# video_in_gps_mems.net
KiCad netlist of a schematic drawn in Altium Designer
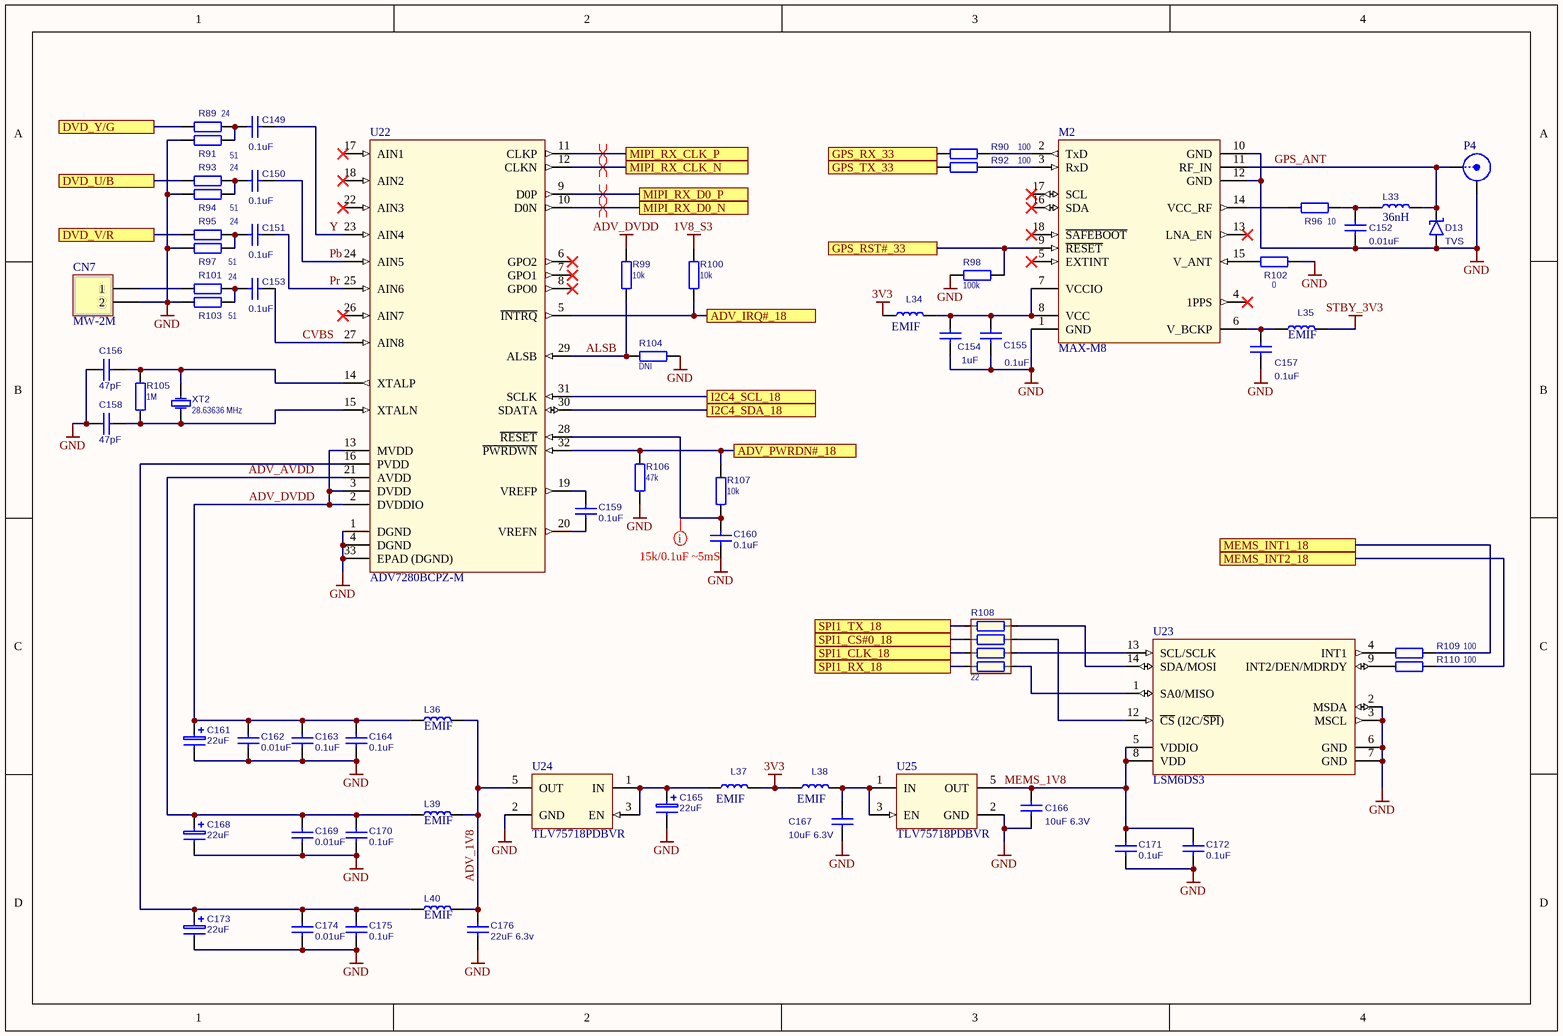
[diagram p0: video_in_gps_mems.SchDoc]

(export (version "E")
  (design (tool "Eeschema 10.0.6"))
  (components
    (comp (ref "C149")
      (value "0.1uF")
      (footprint "Capacitors:C0603")
      (description "CAP_NPOL")
      (fields (field (name "Comment") "C1608X7R1H104K080AA"))
      (libsource (lib "capacitors") (part "CAP_NPOL"))
    )
    (comp (ref "C150")
      (value "0.1uF")
      (footprint "Capacitors:C0603")
      (description "CAP_NPOL")
      (fields (field (name "Comment") "C1608X7R1H104K080AA"))
      (libsource (lib "capacitors") (part "CAP_NPOL"))
    )
    (comp (ref "C151")
      (value "0.1uF")
      (footprint "Capacitors:C0603")
      (description "CAP_NPOL")
      (fields (field (name "Comment") "C1608X7R1H104K080AA"))
      (libsource (lib "capacitors") (part "CAP_NPOL"))
    )
    (comp (ref "C152")
      (value "0.01uF")
      (footprint "Capacitors:C0603")
      (description "CAP_NPOL")
      (fields (field (name "Comment") "CL10B103KB8NNNC"))
      (libsource (lib "capacitors") (part "CAP_NPOL"))
    )
    (comp (ref "C153")
      (value "0.1uF")
      (footprint "Capacitors:C0603")
      (description "CAP_NPOL")
      (fields (field (name "Comment") "C1608X7R1H104K080AA"))
      (libsource (lib "capacitors") (part "CAP_NPOL"))
    )
    (comp (ref "C154")
      (value "1uF")
      (footprint "Capacitors:C0603")
      (description "CAP_NPOL")
      (fields (field (name "Comment") "CC0603KRX7R9BB105"))
      (libsource (lib "capacitors") (part "CAP_NPOL"))
    )
    (comp (ref "C155")
      (value "0.1uF")
      (footprint "Capacitors:C0603")
      (description "CAP_NPOL")
      (fields (field (name "Comment") "C1608X7R1H104K080AA"))
      (libsource (lib "capacitors") (part "CAP_NPOL"))
    )
    (comp (ref "C156")
      (value "47pF")
      (footprint "Capacitors:C0603")
      (description "CAP_NPOL")
      (fields (field (name "Comment") "CC0603JRNPO9BN470"))
      (libsource (lib "capacitors") (part "CAP_NPOL"))
    )
    (comp (ref "C157")
      (value "0.1uF")
      (footprint "Capacitors:C0603")
      (description "CAP_NPOL")
      (fields (field (name "Comment") "C1608X7R1H104K080AA"))
      (libsource (lib "capacitors") (part "CAP_NPOL"))
    )
    (comp (ref "C158")
      (value "47pF")
      (footprint "Capacitors:C0603")
      (description "CAP_NPOL")
      (fields (field (name "Comment") "CC0603JRNPO9BN470"))
      (libsource (lib "capacitors") (part "CAP_NPOL"))
    )
    (comp (ref "C159")
      (value "0.1uF")
      (footprint "Capacitors:C0603")
      (description "CAP_NPOL")
      (fields (field (name "Comment") "C1608X7R1H104K080AA"))
      (libsource (lib "capacitors") (part "CAP_NPOL"))
    )
    (comp (ref "C160")
      (value "0.1uF")
      (footprint "Capacitors:C0603")
      (description "CAP_NPOL")
      (fields (field (name "Comment") "C1608X7R1H104K080AA"))
      (libsource (lib "capacitors") (part "CAP_NPOL"))
    )
    (comp (ref "C161")
      (value "22uF")
      (footprint "Capacitors:TANTAL-A-1206")
      (description "CAP_POL")
      (fields (field (name "Comment") "293D226X9010A2TE3"))
      (libsource (lib "capacitors") (part "CAP_POL"))
    )
    (comp (ref "C162")
      (value "0.01uF")
      (footprint "Capacitors:C0603")
      (description "CAP_NPOL")
      (fields (field (name "Comment") "CL10B103KB8NNNC"))
      (libsource (lib "capacitors") (part "CAP_NPOL"))
    )
    (comp (ref "C163")
      (value "0.1uF")
      (footprint "Capacitors:C0603")
      (description "CAP_NPOL")
      (fields (field (name "Comment") "C1608X7R1H104K080AA"))
      (libsource (lib "capacitors") (part "CAP_NPOL"))
    )
    (comp (ref "C164")
      (value "0.1uF")
      (footprint "Capacitors:C0603")
      (description "CAP_NPOL")
      (fields (field (name "Comment") "C1608X7R1H104K080AA"))
      (libsource (lib "capacitors") (part "CAP_NPOL"))
    )
    (comp (ref "C165")
      (value "22uF")
      (footprint "Capacitors:TANTAL-A-1206")
      (description "CAP_POL")
      (fields (field (name "Comment") "293D226X9010A2TE3"))
      (libsource (lib "capacitors") (part "CAP_POL"))
    )
    (comp (ref "C166")
      (value "10uF 6.3V")
      (footprint "Capacitors:C0603")
      (description "CAP_NPOL")
      (fields (field (name "Comment") "CC0603MRX5R5BB106"))
      (libsource (lib "capacitors") (part "CAP_NPOL"))
    )
    (comp (ref "C167")
      (value "10uF 6.3V")
      (footprint "Capacitors:C0603")
      (description "CAP_NPOL")
      (fields (field (name "Comment") "CC0603MRX5R5BB106"))
      (libsource (lib "capacitors") (part "CAP_NPOL"))
    )
    (comp (ref "C168")
      (value "22uF")
      (footprint "Capacitors:TANTAL-A-1206")
      (description "CAP_POL")
      (fields (field (name "Comment") "293D226X9010A2TE3"))
      (libsource (lib "capacitors") (part "CAP_POL"))
    )
    (comp (ref "C169")
      (value "0.01uF")
      (footprint "Capacitors:C0603")
      (description "CAP_NPOL")
      (fields (field (name "Comment") "CL10B103KB8NNNC"))
      (libsource (lib "capacitors") (part "CAP_NPOL"))
    )
    (comp (ref "C170")
      (value "0.1uF")
      (footprint "Capacitors:C0603")
      (description "CAP_NPOL")
      (fields (field (name "Comment") "C1608X7R1H104K080AA"))
      (libsource (lib "capacitors") (part "CAP_NPOL"))
    )
    (comp (ref "C171")
      (value "0.1uF")
      (footprint "Capacitors:C0603")
      (description "CAP_NPOL")
      (fields (field (name "Comment") "C1608X7R1H104K080AA"))
      (libsource (lib "capacitors") (part "CAP_NPOL"))
    )
    (comp (ref "C172")
      (value "0.1uF")
      (footprint "Capacitors:C0603")
      (description "CAP_NPOL")
      (fields (field (name "Comment") "C1608X7R1H104K080AA"))
      (libsource (lib "capacitors") (part "CAP_NPOL"))
    )
    (comp (ref "C173")
      (value "22uF")
      (footprint "Capacitors:TANTAL-A-1206")
      (description "CAP_POL")
      (fields (field (name "Comment") "293D226X9010A2TE3"))
      (libsource (lib "capacitors") (part "CAP_POL"))
    )
    (comp (ref "C174")
      (value "0.01uF")
      (footprint "Capacitors:C0603")
      (description "CAP_NPOL")
      (fields (field (name "Comment") "CL10B103KB8NNNC"))
      (libsource (lib "capacitors") (part "CAP_NPOL"))
    )
    (comp (ref "C175")
      (value "0.1uF")
      (footprint "Capacitors:C0603")
      (description "CAP_NPOL")
      (fields (field (name "Comment") "C1608X7R1H104K080AA"))
      (libsource (lib "capacitors") (part "CAP_NPOL"))
    )
    (comp (ref "C176")
      (value "22uF 6.3v")
      (footprint "Capacitors:C0805")
      (description "CAP_NPOL")
      (fields (field (name "Comment") "CL21A226MQQNNNE"))
      (libsource (lib "capacitors") (part "CAP_NPOL"))
    )
    (comp (ref "CN7")
      (value "MW-2M")
      (footprint "MW-2M")
      (description "Header, 2-Pin")
      (fields (field (name "PUBLISHER") "Altium Limited"))
      (libsource (lib "HDR") (part "HDR 2"))
    )
    (comp (ref "D13")
      (value "TVS")
      (footprint "SOD-323")
      (description "CDSOD323-T05LC")
      (libsource (lib "diodes") (part "SHOTTKY"))
    )
    (comp (ref "L33")
      (value "36nH")
      (footprint "IND0603")
      (description "IND_WO_IRON")
      (fields (field (name "Comment") "LQW18AN36NG00D"))
      (libsource (lib "inductors") (part "IND_WO_IRON"))
    )
    (comp (ref "L34")
      (value "EMIF")
      (footprint "IND0603")
      (description "IND_WO_IRON")
      (fields (field (name "Comment") "BLM18AG102SN1D"))
      (libsource (lib "inductors") (part "IND_WO_IRON"))
    )
    (comp (ref "L35")
      (value "EMIF")
      (footprint "IND0603")
      (description "IND_WO_IRON")
      (fields (field (name "Comment") "BLM18AG102SN1D"))
      (libsource (lib "inductors") (part "IND_WO_IRON"))
    )
    (comp (ref "L36")
      (value "EMIF")
      (footprint "IND0603")
      (description "IND_WO_IRON")
      (fields (field (name "Comment") "BLM18AG102SN1D"))
      (libsource (lib "inductors") (part "IND_WO_IRON"))
    )
    (comp (ref "L37")
      (value "EMIF")
      (footprint "IND0603")
      (description "IND_WO_IRON")
      (fields (field (name "Comment") "BLM18AG102SN1D"))
      (libsource (lib "inductors") (part "IND_WO_IRON"))
    )
    (comp (ref "L38")
      (value "EMIF")
      (footprint "IND0603")
      (description "IND_WO_IRON")
      (fields (field (name "Comment") "BLM18AG102SN1D"))
      (libsource (lib "inductors") (part "IND_WO_IRON"))
    )
    (comp (ref "L39")
      (value "EMIF")
      (footprint "IND0603")
      (description "IND_WO_IRON")
      (fields (field (name "Comment") "BLM18AG102SN1D"))
      (libsource (lib "inductors") (part "IND_WO_IRON"))
    )
    (comp (ref "L40")
      (value "EMIF")
      (footprint "IND0603")
      (description "IND_WO_IRON")
      (fields (field (name "Comment") "BLM18AG102SN1D"))
      (libsource (lib "inductors") (part "IND_WO_IRON"))
    )
    (comp (ref "M2")
      (value "MAX-M8")
      (footprint "GNSS:MAX-M8")
      (description "MAX-M8 concurrent GNSS modules")
      (libsource (lib "GNSS") (part "MAX-M8"))
    )
    (comp (ref "P4")
      (value "I-PEX")
      (footprint "RF:I-PEX")
      (fields (field (name "PUBLISHER") "Altium Limited"))
      (libsource (lib "Miscellaneous Connectors") (part "BNC"))
    )
    (comp (ref "R89")
      (value "24")
      (footprint "R0603")
      (description "RES")
      (libsource (lib "resistors") (part "RESISTOR"))
    )
    (comp (ref "R90")
      (value "100")
      (footprint "R0603")
      (description "RES")
      (libsource (lib "resistors") (part "RESISTOR"))
    )
    (comp (ref "R91")
      (value "51")
      (footprint "R0603")
      (description "RES")
      (libsource (lib "resistors") (part "RESISTOR"))
    )
    (comp (ref "R92")
      (value "100")
      (footprint "R0603")
      (description "RES")
      (libsource (lib "resistors") (part "RESISTOR"))
    )
    (comp (ref "R93")
      (value "24")
      (footprint "R0603")
      (description "RES")
      (libsource (lib "resistors") (part "RESISTOR"))
    )
    (comp (ref "R94")
      (value "51")
      (footprint "R0603")
      (description "RES")
      (libsource (lib "resistors") (part "RESISTOR"))
    )
    (comp (ref "R95")
      (value "24")
      (footprint "R0603")
      (description "RES")
      (libsource (lib "resistors") (part "RESISTOR"))
    )
    (comp (ref "R96")
      (value "10")
      (footprint "R0603")
      (description "RES")
      (libsource (lib "resistors") (part "RESISTOR"))
    )
    (comp (ref "R97")
      (value "51")
      (footprint "R0603")
      (description "RES")
      (libsource (lib "resistors") (part "RESISTOR"))
    )
    (comp (ref "R98")
      (value "100k")
      (footprint "R0603")
      (description "RES")
      (libsource (lib "resistors") (part "RESISTOR"))
    )
    (comp (ref "R99")
      (value "10k")
      (footprint "R0603")
      (description "RES")
      (libsource (lib "resistors") (part "RESISTOR"))
    )
    (comp (ref "R100")
      (value "10k")
      (footprint "R0603")
      (description "RES")
      (libsource (lib "resistors") (part "RESISTOR"))
    )
    (comp (ref "R101")
      (value "24")
      (footprint "R0603")
      (description "RES")
      (libsource (lib "resistors") (part "RESISTOR"))
    )
    (comp (ref "R102")
      (value "0")
      (footprint "R0603")
      (description "RES")
      (libsource (lib "resistors") (part "RESISTOR"))
    )
    (comp (ref "R103")
      (value "51")
      (footprint "R0603")
      (description "RES")
      (libsource (lib "resistors") (part "RESISTOR"))
    )
    (comp (ref "R104")
      (value "DNI")
      (footprint "R0603")
      (description "RES")
      (libsource (lib "resistors") (part "RESISTOR"))
    )
    (comp (ref "R105")
      (value "1M")
      (footprint "R0603")
      (description "RES")
      (libsource (lib "resistors") (part "RESISTOR"))
    )
    (comp (ref "R106")
      (value "47k")
      (footprint "R0603")
      (description "RES")
      (libsource (lib "resistors") (part "RESISTOR"))
    )
    (comp (ref "R107")
      (value "10k")
      (footprint "R0603")
      (description "RES")
      (libsource (lib "resistors") (part "RESISTOR"))
    )
    (comp (ref "R108")
      (value "22")
      (footprint "Resistors:R0804X4")
      (description "ARRAY")
      (fields (field (name "Comment") "TC124-JR-0722RL"))
      (libsource (lib "resistors") (part "ARRAY"))
    )
    (comp (ref "R109")
      (value "100")
      (footprint "R0603")
      (description "RES")
      (libsource (lib "resistors") (part "RESISTOR"))
    )
    (comp (ref "R110")
      (value "100")
      (footprint "R0603")
      (description "RES")
      (libsource (lib "resistors") (part "RESISTOR"))
    )
    (comp (ref "U22")
      (value "ADV7280BCPZ-M")
      (footprint "CP-32-12")
      (description "10-Bit, 4xOversampling SDTV Video Decoder")
      (libsource (lib "ADV7280") (part "ADV7280BCPZ-M"))
    )
    (comp (ref "U23")
      (value "LSM6DS3")
      (footprint "LGA-14 (2.5x3.0x0.86)")
      (description "iNEMO inertial module:\r\n always-on 3D accelerometer and 3D gyroscope")
      (libsource (lib "LSM6DS3") (part "LSM6DS3"))
    )
    (comp (ref "U24")
      (value "TLV75718PDBVR")
      (footprint "SOT-23-5")
      (description "Capacitor-Free, 300-mA, Low-Dropout Regulator with Foldback Current Limit for Portable Devices")
      (libsource (lib "") (part "TLV733P_1"))
    )
    (comp (ref "U25")
      (value "TLV75718PDBVR")
      (footprint "SOT-23-5")
      (description "Capacitor-Free, 300-mA, Low-Dropout Regulator with Foldback Current Limit for Portable Devices")
      (libsource (lib "TLV733P") (part "TLV733P"))
    )
    (comp (ref "XT2")
      (value "28.63636 MHz")
      (footprint "HC-49/S-SMD")
      (description "Xtal")
      (libsource (lib "xtal") (part "XTAL"))
    )
  )
  (nets
    (net (code "1") (name "/ADV_1V8") (class "Default")
      (node (ref "C176") (pin "2") (pinfunction "2_2") (pintype "passive"))
      (node (ref "L36") (pin "2") (pintype "passive"))
      (node (ref "L39") (pin "2") (pintype "passive"))
      (node (ref "L40") (pin "2") (pintype "passive"))
      (node (ref "U24") (pin "5") (pinfunction "OUT_5") (pintype "power_in"))
    )
    (net (code "2") (name "/ADV_AVDD") (class "Default")
      (node (ref "C168") (pin "1") (pinfunction "+_1") (pintype "passive"))
      (node (ref "C169") (pin "1") (pinfunction "1_1") (pintype "passive"))
      (node (ref "C170") (pin "1") (pinfunction "1_1") (pintype "passive"))
      (node (ref "L39") (pin "1") (pintype "passive"))
      (node (ref "U22") (pin "21") (pinfunction "AVDD_21") (pintype "power_in"))
    )
    (net (code "3") (name "/ADV_IRQ#_18") (class "Default")
      (node (ref "R100") (pin "1") (pinfunction "1_1") (pintype "passive"))
      (node (ref "U22") (pin "5") (pinfunction "~{INTRQ}_5") (pintype "output"))
    )
    (net (code "4") (name "/ADV_PWRDN#_18") (class "Default")
      (node (ref "R106") (pin "2") (pinfunction "2_2") (pintype "passive"))
      (node (ref "R107") (pin "1") (pinfunction "1_1") (pintype "passive"))
      (node (ref "U22") (pin "32") (pinfunction "~{PWRDWN}_32") (pintype "input"))
    )
    (net (code "5") (name "/ALSB") (class "Default")
      (node (ref "R104") (pin "2") (pinfunction "2_2") (pintype "passive"))
      (node (ref "R99") (pin "1") (pinfunction "1_1") (pintype "passive"))
      (node (ref "U22") (pin "29") (pinfunction "ALSB_29") (pintype "input"))
    )
    (net (code "6") (name "/CVBS") (class "Default")
      (node (ref "C153") (pin "1") (pinfunction "1_1") (pintype "passive"))
      (node (ref "U22") (pin "27") (pinfunction "AIN8_27") (pintype "input"))
    )
    (net (code "7") (name "/DVD_U{slash}B") (class "Default")
      (node (ref "R93") (pin "2") (pinfunction "2_2") (pintype "passive"))
    )
    (net (code "8") (name "/DVD_V{slash}R") (class "Default")
      (node (ref "R95") (pin "2") (pinfunction "2_2") (pintype "passive"))
    )
    (net (code "9") (name "/DVD_Y{slash}G") (class "Default")
      (node (ref "R89") (pin "2") (pinfunction "2_2") (pintype "passive"))
    )
    (net (code "10") (name "/GPS_ANT") (class "Default")
      (node (ref "D13") (pin "2") (pinfunction "K_2") (pintype "passive"))
      (node (ref "L33") (pin "2") (pintype "passive"))
      (node (ref "M2") (pin "11") (pinfunction "RF_IN_11") (pintype "passive"))
      (node (ref "P4") (pin "1") (pinfunction "X_1") (pintype "passive"))
    )
    (net (code "11") (name "/GPS_RST#_33") (class "Default")
      (node (ref "M2") (pin "9") (pinfunction "~{RESET}_9") (pintype "input"))
      (node (ref "R98") (pin "2") (pinfunction "2_2") (pintype "passive"))
    )
    (net (code "12") (name "/GPS_RX_33") (class "Default")
      (node (ref "R90") (pin "2") (pinfunction "2_2") (pintype "passive"))
    )
    (net (code "13") (name "/GPS_TX_33") (class "Default")
      (node (ref "R92") (pin "2") (pinfunction "2_2") (pintype "passive"))
    )
    (net (code "14") (name "/I2C4_SCL_18") (class "Default")
      (node (ref "U22") (pin "31") (pinfunction "SCLK_31") (pintype "input"))
    )
    (net (code "15") (name "/I2C4_SDA_18") (class "Default")
      (node (ref "U22") (pin "30") (pinfunction "SDATA_30") (pintype "bidirectional"))
    )
    (net (code "16") (name "/MEMS_1V8") (class "Default")
      (node (ref "C166") (pin "1") (pinfunction "1_1") (pintype "passive"))
      (node (ref "C171") (pin "1") (pinfunction "1_1") (pintype "passive"))
      (node (ref "C172") (pin "1") (pinfunction "1_1") (pintype "passive"))
      (node (ref "U23") (pin "5") (pinfunction "VDDIO_5") (pintype "passive"))
      (node (ref "U23") (pin "8") (pinfunction "VDD_8") (pintype "power_in"))
      (node (ref "U25") (pin "5") (pinfunction "OUT_5") (pintype "power_in"))
    )
    (net (code "17") (name "/MEMS_INT1_18") (class "Default")
      (node (ref "R109") (pin "1") (pinfunction "1_1") (pintype "passive"))
    )
    (net (code "18") (name "/MEMS_INT2_18") (class "Default")
      (node (ref "R110") (pin "1") (pinfunction "1_1") (pintype "passive"))
    )
    (net (code "19") (name "/MIPI_RX_CLK_N") (class "Default")
      (node (ref "U22") (pin "12") (pinfunction "CLKN_12") (pintype "output"))
    )
    (net (code "20") (name "/MIPI_RX_CLK_P") (class "Default")
      (node (ref "U22") (pin "11") (pinfunction "CLKP_11") (pintype "output"))
    )
    (net (code "21") (name "/MIPI_RX_D0_N") (class "Default")
      (node (ref "U22") (pin "10") (pinfunction "D0N_10") (pintype "output"))
    )
    (net (code "22") (name "/MIPI_RX_D0_P") (class "Default")
      (node (ref "U22") (pin "9") (pinfunction "D0P_9") (pintype "output"))
    )
    (net (code "23") (name "/Pb") (class "Default")
      (node (ref "C150") (pin "1") (pinfunction "1_1") (pintype "passive"))
      (node (ref "U22") (pin "24") (pinfunction "AIN5_24") (pintype "input"))
    )
    (net (code "24") (name "/Pr") (class "Default")
      (node (ref "C151") (pin "1") (pinfunction "1_1") (pintype "passive"))
      (node (ref "U22") (pin "25") (pinfunction "AIN6_25") (pintype "input"))
    )
    (net (code "25") (name "/SPI1_CLK_18") (class "Default")
      (node (ref "R108") (pin "3") (pinfunction "3_3") (pintype "passive"))
    )
    (net (code "26") (name "/SPI1_CS#0_18") (class "Default")
      (node (ref "R108") (pin "5") (pinfunction "5_5") (pintype "passive"))
    )
    (net (code "27") (name "/SPI1_RX_18") (class "Default")
      (node (ref "R108") (pin "1") (pinfunction "1_1") (pintype "passive"))
    )
    (net (code "28") (name "/SPI1_TX_18") (class "Default")
      (node (ref "R108") (pin "7") (pinfunction "7_7") (pintype "passive"))
    )
    (net (code "29") (name "/Y") (class "Default")
      (node (ref "C149") (pin "1") (pinfunction "1_1") (pintype "passive"))
      (node (ref "U22") (pin "23") (pinfunction "AIN4_23") (pintype "input"))
    )
    (net (code "30") (name "1V8_S3") (class "Default")
      (node (ref "R100") (pin "2") (pinfunction "2_2") (pintype "passive"))
    )
    (net (code "31") (name "3V3") (class "Default")
      (node (ref "L34") (pin "1") (pintype "passive"))
      (node (ref "L37") (pin "2") (pintype "passive"))
      (node (ref "L38") (pin "1") (pintype "passive"))
    )
    (net (code "32") (name "ADV_DVDD") (class "Default")
      (node (ref "C161") (pin "1") (pinfunction "+_1") (pintype "passive"))
      (node (ref "C162") (pin "1") (pinfunction "1_1") (pintype "passive"))
      (node (ref "C163") (pin "1") (pinfunction "1_1") (pintype "passive"))
      (node (ref "C164") (pin "1") (pinfunction "1_1") (pintype "passive"))
      (node (ref "L36") (pin "1") (pintype "passive"))
      (node (ref "R99") (pin "2") (pinfunction "2_2") (pintype "passive"))
      (node (ref "U22") (pin "13") (pinfunction "MVDD_13") (pintype "power_in"))
      (node (ref "U22") (pin "2") (pinfunction "DVDDIO_2") (pintype "power_in"))
      (node (ref "U22") (pin "3") (pinfunction "DVDD_3") (pintype "power_in"))
    )
    (net (code "33") (name "GND") (class "Default")
      (node (ref "C152") (pin "2") (pinfunction "2_2") (pintype "passive"))
      (node (ref "C154") (pin "1") (pinfunction "1_1") (pintype "passive"))
      (node (ref "C155") (pin "2") (pinfunction "2_2") (pintype "passive"))
      (node (ref "C156") (pin "2") (pinfunction "2_2") (pintype "passive"))
      (node (ref "C157") (pin "2") (pinfunction "2_2") (pintype "passive"))
      (node (ref "C158") (pin "2") (pinfunction "2_2") (pintype "passive"))
      (node (ref "C160") (pin "2") (pinfunction "2_2") (pintype "passive"))
      (node (ref "C161") (pin "2") (pinfunction "-_2") (pintype "passive"))
      (node (ref "C162") (pin "2") (pinfunction "2_2") (pintype "passive"))
      (node (ref "C163") (pin "2") (pinfunction "2_2") (pintype "passive"))
      (node (ref "C164") (pin "2") (pinfunction "2_2") (pintype "passive"))
      (node (ref "C165") (pin "2") (pinfunction "-_2") (pintype "passive"))
      (node (ref "C166") (pin "2") (pinfunction "2_2") (pintype "passive"))
      (node (ref "C167") (pin "2") (pinfunction "2_2") (pintype "passive"))
      (node (ref "C168") (pin "2") (pinfunction "-_2") (pintype "passive"))
      (node (ref "C169") (pin "2") (pinfunction "2_2") (pintype "passive"))
      (node (ref "C170") (pin "2") (pinfunction "2_2") (pintype "passive"))
      (node (ref "C171") (pin "2") (pinfunction "2_2") (pintype "passive"))
      (node (ref "C172") (pin "2") (pinfunction "2_2") (pintype "passive"))
      (node (ref "C173") (pin "2") (pinfunction "-_2") (pintype "passive"))
      (node (ref "C174") (pin "2") (pinfunction "2_2") (pintype "passive"))
      (node (ref "C175") (pin "2") (pinfunction "2_2") (pintype "passive"))
      (node (ref "C176") (pin "1") (pinfunction "1_1") (pintype "passive"))
      (node (ref "CN7") (pin "2") (pinfunction "2_2") (pintype "passive"))
      (node (ref "D13") (pin "1") (pinfunction "A_1") (pintype "passive"))
      (node (ref "M2") (pin "1") (pinfunction "GND_1") (pintype "power_in"))
      (node (ref "M2") (pin "10") (pinfunction "GND_10") (pintype "power_in"))
      (node (ref "M2") (pin "12") (pinfunction "GND_12") (pintype "power_in"))
      (node (ref "P4") (pin "2") (pinfunction "Y_2") (pintype "passive"))
      (node (ref "R102") (pin "1") (pinfunction "1_1") (pintype "passive"))
      (node (ref "R103") (pin "1") (pinfunction "1_1") (pintype "passive"))
      (node (ref "R104") (pin "1") (pinfunction "1_1") (pintype "passive"))
      (node (ref "R106") (pin "1") (pinfunction "1_1") (pintype "passive"))
      (node (ref "R91") (pin "1") (pinfunction "1_1") (pintype "passive"))
      (node (ref "R94") (pin "1") (pinfunction "1_1") (pintype "passive"))
      (node (ref "R97") (pin "1") (pinfunction "1_1") (pintype "passive"))
      (node (ref "R98") (pin "1") (pinfunction "1_1") (pintype "passive"))
      (node (ref "U22") (pin "1") (pinfunction "DGND_1") (pintype "power_in"))
      (node (ref "U22") (pin "33") (pinfunction "EPAD_(DGND)_33") (pintype "power_in"))
      (node (ref "U22") (pin "4") (pinfunction "DGND_4") (pintype "power_in"))
      (node (ref "U23") (pin "2") (pinfunction "MSDA_2") (pintype "bidirectional"))
      (node (ref "U23") (pin "3") (pinfunction "MSCL_3") (pintype "output"))
      (node (ref "U23") (pin "6") (pinfunction "GND_6") (pintype "power_in"))
      (node (ref "U23") (pin "7") (pinfunction "GND_7") (pintype "power_in"))
      (node (ref "U24") (pin "2") (pinfunction "GND_2") (pintype "power_in"))
      (node (ref "U25") (pin "2") (pinfunction "GND_2") (pintype "power_in"))
    )
    (net (code "34") (name "Net-(C149-Pad2)") (class "Default")
      (node (ref "C149") (pin "2") (pinfunction "2_2") (pintype "passive"))
      (node (ref "R89") (pin "1") (pinfunction "1_1") (pintype "passive"))
      (node (ref "R91") (pin "2") (pinfunction "2_2") (pintype "passive"))
    )
    (net (code "35") (name "Net-(C150-Pad2)") (class "Default")
      (node (ref "C150") (pin "2") (pinfunction "2_2") (pintype "passive"))
      (node (ref "R93") (pin "1") (pinfunction "1_1") (pintype "passive"))
      (node (ref "R94") (pin "2") (pinfunction "2_2") (pintype "passive"))
    )
    (net (code "36") (name "Net-(C151-Pad2)") (class "Default")
      (node (ref "C151") (pin "2") (pinfunction "2_2") (pintype "passive"))
      (node (ref "R95") (pin "1") (pinfunction "1_1") (pintype "passive"))
      (node (ref "R97") (pin "2") (pinfunction "2_2") (pintype "passive"))
    )
    (net (code "37") (name "Net-(C152-Pad1)") (class "Default")
      (node (ref "C152") (pin "1") (pinfunction "1_1") (pintype "passive"))
      (node (ref "L33") (pin "1") (pintype "passive"))
      (node (ref "R96") (pin "1") (pinfunction "1_1") (pintype "passive"))
    )
    (net (code "38") (name "Net-(C153-Pad2)") (class "Default")
      (node (ref "C153") (pin "2") (pinfunction "2_2") (pintype "passive"))
      (node (ref "R101") (pin "1") (pinfunction "1_1") (pintype "passive"))
      (node (ref "R103") (pin "2") (pinfunction "2_2") (pintype "passive"))
    )
    (net (code "39") (name "Net-(C165-+)") (class "Default")
      (node (ref "C165") (pin "1") (pinfunction "+_1") (pintype "passive"))
      (node (ref "L37") (pin "1") (pintype "passive"))
      (node (ref "U24") (pin "1") (pinfunction "IN_1") (pintype "power_in"))
      (node (ref "U24") (pin "3") (pinfunction "EN_3") (pintype "input"))
    )
    (net (code "40") (name "Net-(C173-+)") (class "Default")
      (node (ref "C173") (pin "1") (pinfunction "+_1") (pintype "passive"))
      (node (ref "C174") (pin "1") (pinfunction "1_1") (pintype "passive"))
      (node (ref "C175") (pin "1") (pinfunction "1_1") (pintype "passive"))
      (node (ref "L40") (pin "1") (pintype "passive"))
      (node (ref "U22") (pin "16") (pinfunction "PVDD_16") (pintype "power_in"))
    )
    (net (code "41") (name "Net-(CN7-Pad1)") (class "Default")
      (node (ref "CN7") (pin "1") (pinfunction "1_1") (pintype "passive"))
      (node (ref "R101") (pin "2") (pinfunction "2_2") (pintype "passive"))
    )
    (net (code "42") (name "Net-(M2-RxD)") (class "Default")
      (node (ref "M2") (pin "3") (pinfunction "RxD_3") (pintype "input"))
      (node (ref "R92") (pin "1") (pinfunction "1_1") (pintype "passive"))
    )
    (net (code "43") (name "Net-(M2-TxD)") (class "Default")
      (node (ref "M2") (pin "2") (pinfunction "TxD_2") (pintype "output"))
      (node (ref "R90") (pin "1") (pinfunction "1_1") (pintype "passive"))
    )
    (net (code "44") (name "Net-(M2-VCC)") (class "Default")
      (node (ref "C154") (pin "2") (pinfunction "2_2") (pintype "passive"))
      (node (ref "C155") (pin "1") (pinfunction "1_1") (pintype "passive"))
      (node (ref "L34") (pin "2") (pintype "passive"))
      (node (ref "M2") (pin "7") (pinfunction "VCCIO_7") (pintype "power_in"))
      (node (ref "M2") (pin "8") (pinfunction "VCC_8") (pintype "power_in"))
    )
    (net (code "45") (name "Net-(M2-VCC_RF)") (class "Default")
      (node (ref "M2") (pin "14") (pinfunction "VCC_RF_14") (pintype "output"))
      (node (ref "R96") (pin "2") (pinfunction "2_2") (pintype "passive"))
    )
    (net (code "46") (name "Net-(M2-V_ANT)") (class "Default")
      (node (ref "M2") (pin "15") (pinfunction "V_ANT_15") (pintype "input"))
      (node (ref "R102") (pin "2") (pinfunction "2_2") (pintype "passive"))
    )
    (net (code "47") (name "Net-(M2-V_BCKP)") (class "Default")
      (node (ref "C157") (pin "1") (pinfunction "1_1") (pintype "passive"))
      (node (ref "L35") (pin "1") (pintype "passive"))
      (node (ref "M2") (pin "6") (pinfunction "V_BCKP_6") (pintype "power_in"))
    )
    (net (code "48") (name "Net-(U22-VREFN)") (class "Default")
      (node (ref "C159") (pin "2") (pinfunction "2_2") (pintype "passive"))
      (node (ref "U22") (pin "20") (pinfunction "VREFN_20") (pintype "output"))
    )
    (net (code "49") (name "Net-(U22-VREFP)") (class "Default")
      (node (ref "C159") (pin "1") (pinfunction "1_1") (pintype "passive"))
      (node (ref "U22") (pin "19") (pinfunction "VREFP_19") (pintype "output"))
    )
    (net (code "50") (name "Net-(U22-XTALN)") (class "Default")
      (node (ref "C158") (pin "1") (pinfunction "1_1") (pintype "passive"))
      (node (ref "R105") (pin "2") (pinfunction "2_2") (pintype "passive"))
      (node (ref "U22") (pin "15") (pinfunction "XTALN_15") (pintype "input"))
      (node (ref "XT2") (pin "2") (pintype "passive"))
    )
    (net (code "51") (name "Net-(U22-XTALP)") (class "Default")
      (node (ref "C156") (pin "1") (pinfunction "1_1") (pintype "passive"))
      (node (ref "R105") (pin "1") (pinfunction "1_1") (pintype "passive"))
      (node (ref "U22") (pin "14") (pinfunction "XTALP_14") (pintype "output"))
      (node (ref "XT2") (pin "1") (pintype "passive"))
    )
    (net (code "52") (name "Net-(U22-~{RESET})") (class "Default")
      (node (ref "C160") (pin "1") (pinfunction "1_1") (pintype "passive"))
      (node (ref "R107") (pin "2") (pinfunction "2_2") (pintype "passive"))
      (node (ref "U22") (pin "28") (pinfunction "~{RESET}_28") (pintype "input"))
    )
    (net (code "53") (name "Net-(U23-INT1)") (class "Default")
      (node (ref "R109") (pin "2") (pinfunction "2_2") (pintype "passive"))
      (node (ref "U23") (pin "4") (pinfunction "INT1_4") (pintype "output"))
    )
    (net (code "54") (name "Net-(U23-INT2{slash}DEN{slash}MDRDY)") (class "Default")
      (node (ref "R110") (pin "2") (pinfunction "2_2") (pintype "passive"))
      (node (ref "U23") (pin "9") (pinfunction "INT2/DEN/MDRDY_9") (pintype "bidirectional"))
    )
    (net (code "55") (name "Net-(U23-SA0{slash}MISO)") (class "Default")
      (node (ref "R108") (pin "2") (pinfunction "2_2") (pintype "passive"))
      (node (ref "U23") (pin "1") (pinfunction "SA0/MISO_1") (pintype "bidirectional"))
    )
    (net (code "56") (name "Net-(U23-SCL{slash}SCLK)") (class "Default")
      (node (ref "R108") (pin "4") (pinfunction "4_4") (pintype "passive"))
      (node (ref "U23") (pin "13") (pinfunction "SCL/SCLK_13") (pintype "input"))
    )
    (net (code "57") (name "Net-(U23-SDA{slash}MOSI)") (class "Default")
      (node (ref "R108") (pin "8") (pinfunction "8_8") (pintype "passive"))
      (node (ref "U23") (pin "14") (pinfunction "SDA/MOSI_14") (pintype "bidirectional"))
    )
    (net (code "58") (name "Net-(U23-~{CS}_(I2C{slash}~{SPI}))") (class "Default")
      (node (ref "R108") (pin "6") (pinfunction "6_6") (pintype "passive"))
      (node (ref "U23") (pin "12") (pinfunction "~{CS}_(I2C/~{SPI})_12") (pintype "input"))
    )
    (net (code "59") (name "Net-(U25-EN)") (class "Default")
      (node (ref "C167") (pin "1") (pinfunction "1_1") (pintype "passive"))
      (node (ref "L38") (pin "2") (pintype "passive"))
      (node (ref "U25") (pin "1") (pinfunction "IN_1") (pintype "power_in"))
      (node (ref "U25") (pin "3") (pinfunction "EN_3") (pintype "input"))
    )
    (net (code "60") (name "STBY_3V3") (class "Default") (node (ref "L35") (pin "2") (pintype "passive")))
    (net (code "61") (name "unconnected-(M2-1PPS-Pad4)") (class "Default")
      (node (ref "M2") (pin "4") (pinfunction "1PPS_4") (pintype "output+no_connect"))
    )
    (net (code "62") (name "unconnected-(M2-EXTINT-Pad5)") (class "Default")
      (node (ref "M2") (pin "5") (pinfunction "EXTINT_5") (pintype "input+no_connect"))
    )
    (net (code "63") (name "unconnected-(M2-LNA_EN-Pad13)") (class "Default")
      (node (ref "M2") (pin "13") (pinfunction "LNA_EN_13") (pintype "output+no_connect"))
    )
    (net (code "64") (name "unconnected-(M2-SCL-Pad17)") (class "Default")
      (node (ref "M2") (pin "17") (pinfunction "SCL_17") (pintype "bidirectional+no_connect"))
    )
    (net (code "65") (name "unconnected-(M2-SDA-Pad16)") (class "Default")
      (node (ref "M2") (pin "16") (pinfunction "SDA_16") (pintype "bidirectional+no_connect"))
    )
    (net (code "66") (name "unconnected-(M2-~{SAFEBOOT}-Pad18)") (class "Default")
      (node (ref "M2") (pin "18") (pinfunction "~{SAFEBOOT}_18") (pintype "input+no_connect"))
    )
    (net (code "67") (name "unconnected-(U22-AIN1-Pad17)") (class "Default")
      (node (ref "U22") (pin "17") (pinfunction "AIN1_17") (pintype "input+no_connect"))
    )
    (net (code "68") (name "unconnected-(U22-AIN2-Pad18)") (class "Default")
      (node (ref "U22") (pin "18") (pinfunction "AIN2_18") (pintype "input+no_connect"))
    )
    (net (code "69") (name "unconnected-(U22-AIN3-Pad22)") (class "Default")
      (node (ref "U22") (pin "22") (pinfunction "AIN3_22") (pintype "input+no_connect"))
    )
    (net (code "70") (name "unconnected-(U22-AIN7-Pad26)") (class "Default")
      (node (ref "U22") (pin "26") (pinfunction "AIN7_26") (pintype "input+no_connect"))
    )
    (net (code "71") (name "unconnected-(U22-GPO0-Pad8)") (class "Default")
      (node (ref "U22") (pin "8") (pinfunction "GPO0_8") (pintype "output+no_connect"))
    )
    (net (code "72") (name "unconnected-(U22-GPO1-Pad7)") (class "Default")
      (node (ref "U22") (pin "7") (pinfunction "GPO1_7") (pintype "output+no_connect"))
    )
    (net (code "73") (name "unconnected-(U22-GPO2-Pad6)") (class "Default")
      (node (ref "U22") (pin "6") (pinfunction "GPO2_6") (pintype "output+no_connect"))
    )
  )
)
